# 25_Clocks_1.net
KiCad netlist of a schematic drawn in Altium Designer
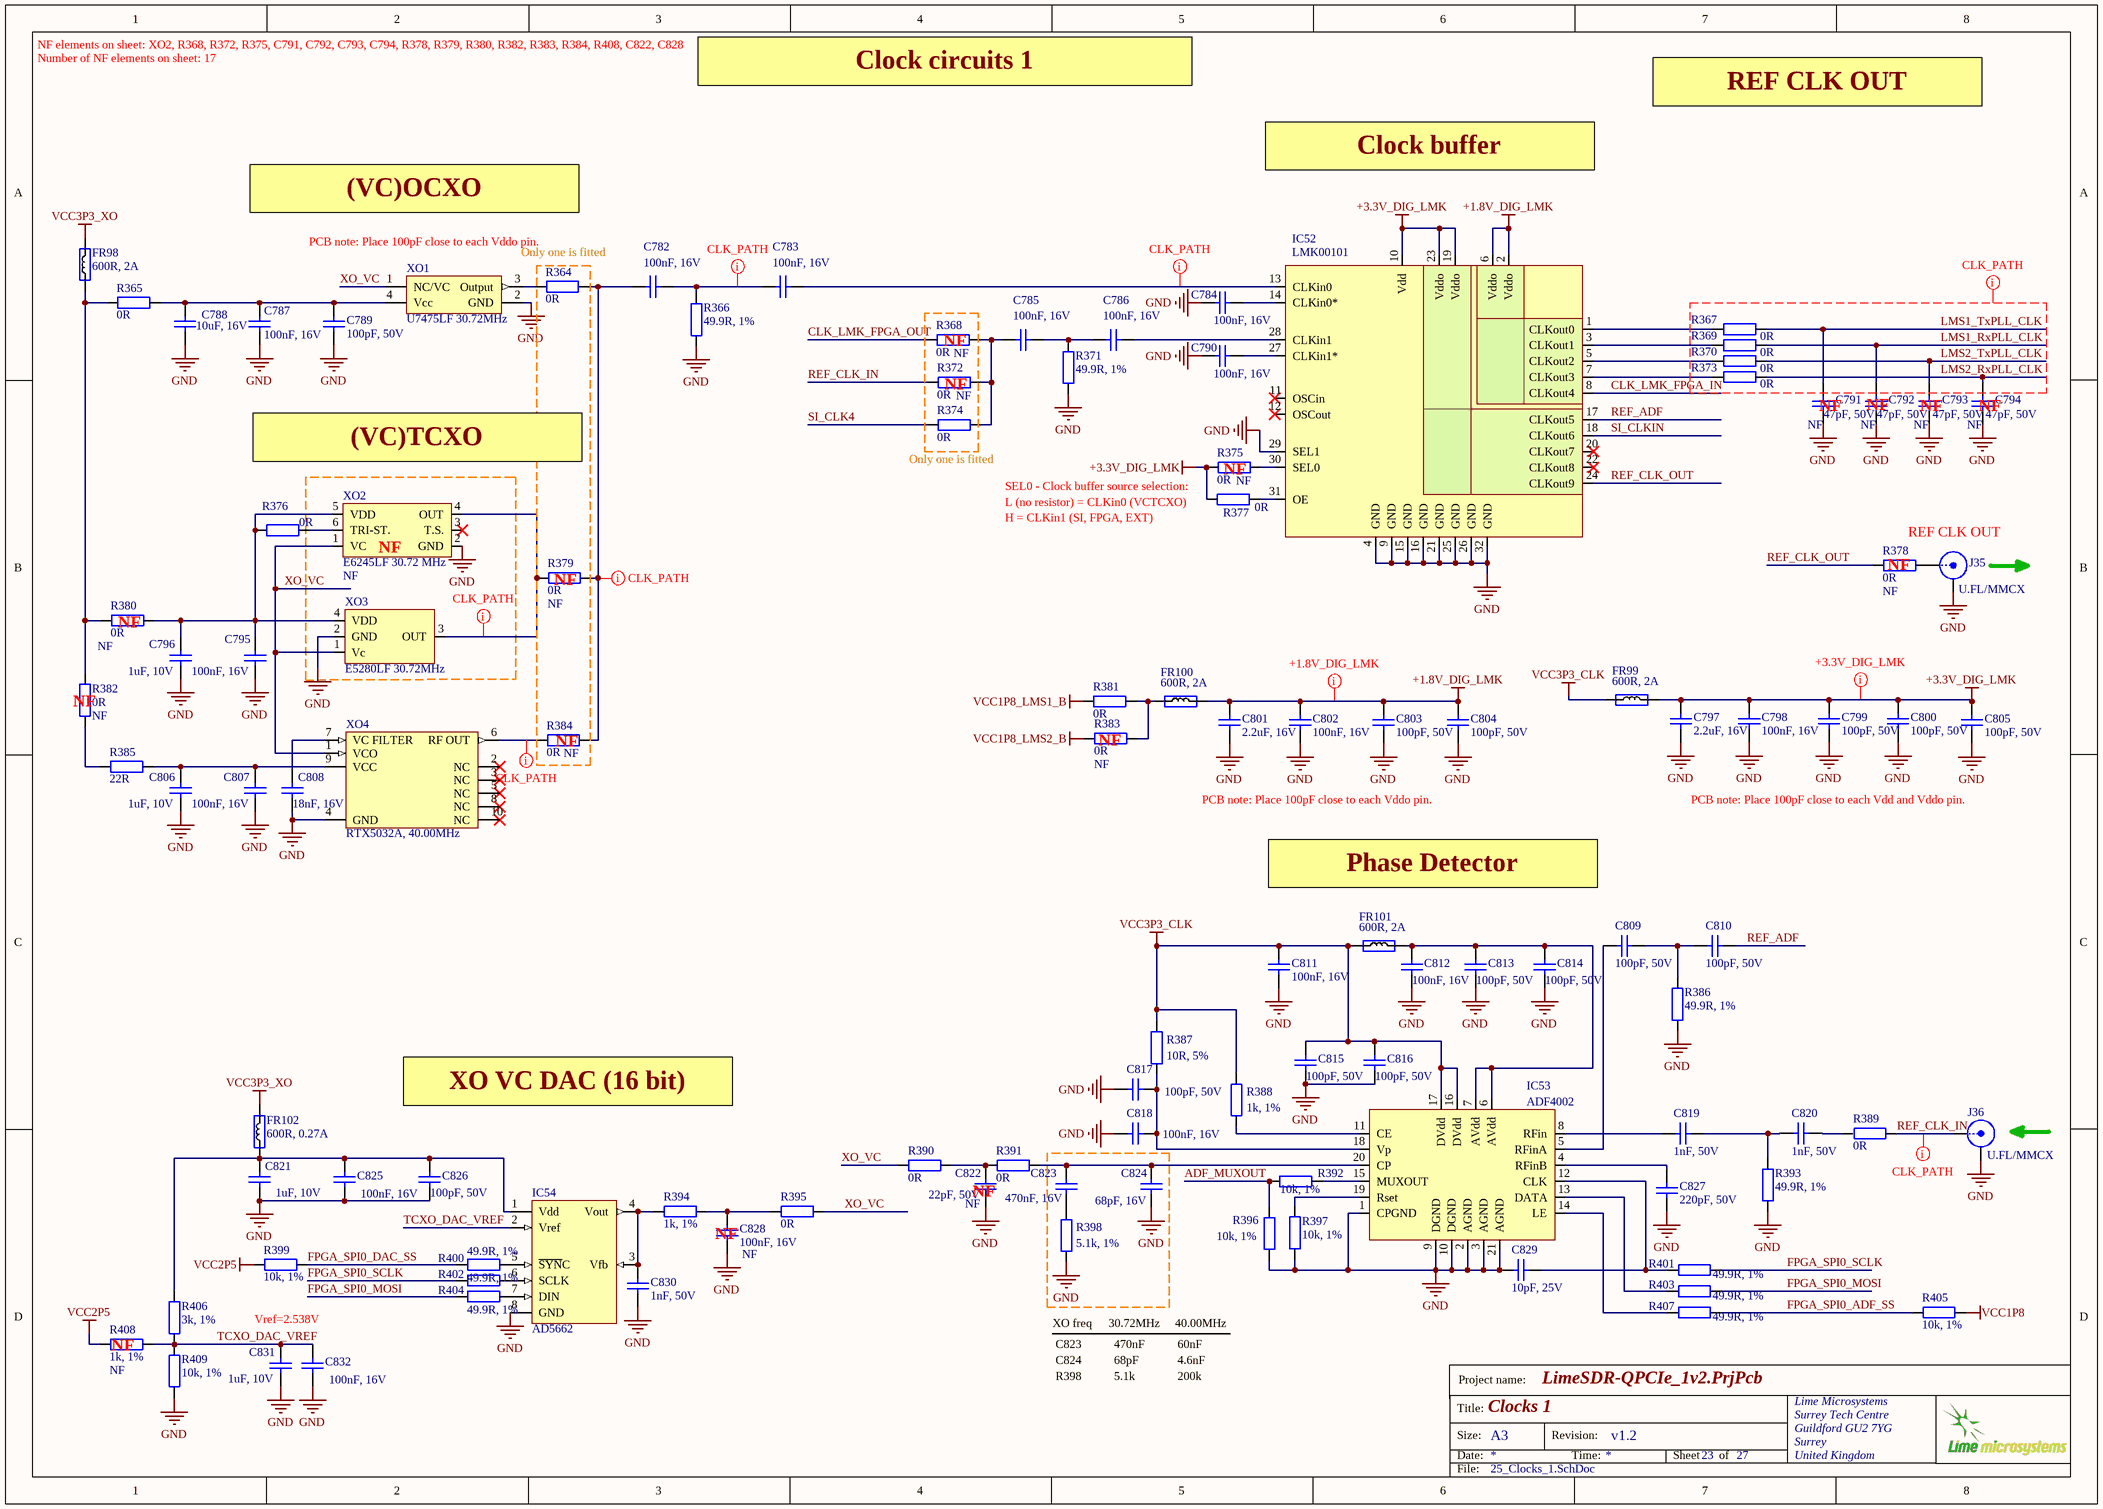
[diagram p0: 25_Clocks_1.SchDoc]

(export (version "E")
  (design (tool "Eeschema 10.0.6"))
  (components
    (comp (ref "C782")
      (value "100nF, 16V")
      (footprint "CAP0402")
      (fields
        (field (name "MANUFACTURER") "Murata Electronics")
        (field (name "TOLERANCE") "10 %")
        (field (name "MANUFACTURER PART NUMBER") "GRM155R71C104KA88D")
      )
      (libsource (lib "LimeMicroAltiumLib_schLib") (part "Cap_0402"))
    )
    (comp (ref "C783")
      (value "100nF, 16V")
      (footprint "CAP0402")
      (fields
        (field (name "MANUFACTURER") "Murata Electronics")
        (field (name "TOLERANCE") "10 %")
        (field (name "MANUFACTURER PART NUMBER") "GRM155R71C104KA88D")
      )
      (libsource (lib "LimeMicroAltiumLib_schLib") (part "Cap_0402"))
    )
    (comp (ref "C784")
      (value "100nF, 16V")
      (footprint "CAP0402")
      (fields
        (field (name "MANUFACTURER") "Murata Electronics")
        (field (name "TOLERANCE") "10 %")
        (field (name "MANUFACTURER PART NUMBER") "GRM155R71C104KA88D")
      )
      (libsource (lib "LimeMicroAltiumLib_schLib") (part "Cap_0402"))
    )
    (comp (ref "C785")
      (value "100nF, 16V")
      (footprint "CAP0402")
      (fields
        (field (name "MANUFACTURER") "Murata Electronics")
        (field (name "TOLERANCE") "10 %")
        (field (name "MANUFACTURER PART NUMBER") "GRM155R71C104KA88D")
      )
      (libsource (lib "LimeMicroAltiumLib_schLib") (part "Cap_0402"))
    )
    (comp (ref "C786")
      (value "100nF, 16V")
      (footprint "CAP0402")
      (fields
        (field (name "MANUFACTURER") "Murata Electronics")
        (field (name "TOLERANCE") "10 %")
        (field (name "MANUFACTURER PART NUMBER") "GRM155R71C104KA88D")
      )
      (libsource (lib "LimeMicroAltiumLib_schLib") (part "Cap_0402"))
    )
    (comp (ref "C787")
      (value "100nF, 16V")
      (footprint "CAP0402")
      (fields
        (field (name "MANUFACTURER") "Murata Electronics")
        (field (name "TOLERANCE") "10 %")
        (field (name "MANUFACTURER PART NUMBER") "GRM155R71C104KA88D")
      )
      (libsource (lib "LimeMicroAltiumLib_schLib") (part "Cap_0402"))
    )
    (comp (ref "C788")
      (value "10uF, 16V")
      (footprint "CAP0603")
      (fields (field (name "MANUFACTURER") "Yageo") (field (name "TOLERANCE") "±20%"))
      (libsource (lib "LimeMicroAltiumLib_schLib") (part "Cap_0603"))
    )
    (comp (ref "C789")
      (value "100pF, 50V")
      (footprint "CAP0402")
      (fields (field (name "TOLERANCE") "±5%") (field (name "MANUFACTURER") "Yageo"))
      (libsource (lib "LimeMicroAltiumLib_schLib") (part "Cap_0402"))
    )
    (comp (ref "C790")
      (value "100nF, 16V")
      (footprint "CAP0402")
      (fields
        (field (name "MANUFACTURER") "Murata Electronics")
        (field (name "TOLERANCE") "10 %")
        (field (name "MANUFACTURER PART NUMBER") "GRM155R71C104KA88D")
      )
      (libsource (lib "LimeMicroAltiumLib_schLib") (part "Cap_0402"))
    )
    (comp (ref "C791")
      (value "47pF, 50V")
      (footprint "CAP0402")
      (fields
        (field (name "TOLERANCE") "±1%")
        (field (name "MANUFACTURER") "TDK Corporation")
        (field (name "ASSEMBLY INFO") "NF")
      )
      (libsource (lib "LimeMicroAltiumLib_schLib") (part "Cap_0402"))
    )
    (comp (ref "C792")
      (value "47pF, 50V")
      (footprint "CAP0402")
      (fields
        (field (name "TOLERANCE") "±1%")
        (field (name "MANUFACTURER") "TDK Corporation")
        (field (name "ASSEMBLY INFO") "NF")
      )
      (libsource (lib "LimeMicroAltiumLib_schLib") (part "Cap_0402"))
    )
    (comp (ref "C793")
      (value "47pF, 50V")
      (footprint "CAP0402")
      (fields
        (field (name "TOLERANCE") "±1%")
        (field (name "MANUFACTURER") "TDK Corporation")
        (field (name "ASSEMBLY INFO") "NF")
      )
      (libsource (lib "LimeMicroAltiumLib_schLib") (part "Cap_0402"))
    )
    (comp (ref "C794")
      (value "47pF, 50V")
      (footprint "CAP0402")
      (fields
        (field (name "TOLERANCE") "±1%")
        (field (name "MANUFACTURER") "TDK Corporation")
        (field (name "ASSEMBLY INFO") "NF")
      )
      (libsource (lib "LimeMicroAltiumLib_schLib") (part "Cap_0402"))
    )
    (comp (ref "C795")
      (value "100nF, 16V")
      (footprint "CAP0402")
      (fields
        (field (name "MANUFACTURER") "Murata Electronics")
        (field (name "TOLERANCE") "10 %")
        (field (name "MANUFACTURER PART NUMBER") "GRM155R71C104KA88D")
      )
      (libsource (lib "LimeMicroAltiumLib_schLib") (part "Cap_0402"))
    )
    (comp (ref "C796")
      (value "1uF, 10V")
      (footprint "CAP0402")
      (fields (field (name "MANUFACTURER") "TDK"))
      (libsource (lib "LimeMicroAltiumLib_schLib") (part "Cap_0402"))
    )
    (comp (ref "C797")
      (value "2.2uF, 16V")
      (footprint "CAP0402")
      (description "CAP CER 2.2UF 16V 10% X5R 0402")
      (fields (field (name "MANUFACTURER") "TDK Corporation") (field (name "TOLERANCE") "±20%"))
      (libsource (lib "LimeMicroAltiumLib_schLib") (part "Cap_0402"))
    )
    (comp (ref "C798")
      (value "100nF, 16V")
      (footprint "CAP0402")
      (fields
        (field (name "MANUFACTURER") "Murata Electronics")
        (field (name "TOLERANCE") "10 %")
        (field (name "MANUFACTURER PART NUMBER") "GRM155R71C104KA88D")
      )
      (libsource (lib "LimeMicroAltiumLib_schLib") (part "Cap_0402"))
    )
    (comp (ref "C799")
      (value "100pF, 50V")
      (footprint "CAP0402")
      (fields (field (name "MANUFACTURER") "Yageo") (field (name "TOLERANCE") "±5%"))
      (libsource (lib "LimeMicroAltiumLib_schLib") (part "Cap_0402"))
    )
    (comp (ref "C800")
      (value "100pF, 50V")
      (footprint "CAP0402")
      (fields (field (name "MANUFACTURER") "Yageo") (field (name "TOLERANCE") "±5%"))
      (libsource (lib "LimeMicroAltiumLib_schLib") (part "Cap_0402"))
    )
    (comp (ref "C801")
      (value "2.2uF, 16V")
      (footprint "CAP0402")
      (description "CAP CER 2.2UF 16V 10% X5R 0402")
      (fields (field (name "MANUFACTURER") "TDK Corporation") (field (name "TOLERANCE") "±20%"))
      (libsource (lib "LimeMicroAltiumLib_schLib") (part "Cap_0402"))
    )
    (comp (ref "C802")
      (value "100nF, 16V")
      (footprint "CAP0402")
      (fields
        (field (name "MANUFACTURER") "Murata Electronics")
        (field (name "TOLERANCE") "10 %")
        (field (name "MANUFACTURER PART NUMBER") "GRM155R71C104KA88D")
      )
      (libsource (lib "LimeMicroAltiumLib_schLib") (part "Cap_0402"))
    )
    (comp (ref "C803")
      (value "100pF, 50V")
      (footprint "CAP0402")
      (fields (field (name "MANUFACTURER") "Yageo") (field (name "TOLERANCE") "±5%"))
      (libsource (lib "LimeMicroAltiumLib_schLib") (part "Cap_0402"))
    )
    (comp (ref "C804")
      (value "100pF, 50V")
      (footprint "CAP0402")
      (fields (field (name "MANUFACTURER") "Yageo") (field (name "TOLERANCE") "±5%"))
      (libsource (lib "LimeMicroAltiumLib_schLib") (part "Cap_0402"))
    )
    (comp (ref "C805")
      (value "100pF, 50V")
      (footprint "CAP0402")
      (fields (field (name "MANUFACTURER") "Yageo") (field (name "TOLERANCE") "±5%"))
      (libsource (lib "LimeMicroAltiumLib_schLib") (part "Cap_0402"))
    )
    (comp (ref "C806")
      (value "1uF, 10V")
      (footprint "CAP0402")
      (fields (field (name "MANUFACTURER") "TDK"))
      (libsource (lib "LimeMicroAltiumLib_schLib") (part "Cap_0402"))
    )
    (comp (ref "C807")
      (value "100nF, 16V")
      (footprint "CAP0402")
      (fields
        (field (name "MANUFACTURER") "Murata Electronics")
        (field (name "TOLERANCE") "10 %")
        (field (name "MANUFACTURER PART NUMBER") "GRM155R71C104KA88D")
      )
      (libsource (lib "LimeMicroAltiumLib_schLib") (part "Cap_0402"))
    )
    (comp (ref "C808")
      (value "18nF, 16V")
      (footprint "CAP0402")
      (fields (field (name "MANUFACTURER") "Yageo") (field (name "TOLERANCE") "±10%"))
      (libsource (lib "LimeMicroAltiumLib_schLib") (part "Cap_0402"))
    )
    (comp (ref "C809")
      (value "100pF, 50V")
      (footprint "CAP0402")
      (fields (field (name "MANUFACTURER") "Yageo") (field (name "TOLERANCE") "±5%"))
      (libsource (lib "LimeMicroAltiumLib_schLib") (part "Cap_0402"))
    )
    (comp (ref "C810")
      (value "100pF, 50V")
      (footprint "CAP0402")
      (fields (field (name "MANUFACTURER") "Yageo") (field (name "TOLERANCE") "±5%"))
      (libsource (lib "LimeMicroAltiumLib_schLib") (part "Cap_0402"))
    )
    (comp (ref "C811")
      (value "100nF, 16V")
      (footprint "CAP0402")
      (fields
        (field (name "MANUFACTURER") "Murata Electronics")
        (field (name "TOLERANCE") "10 %")
        (field (name "MANUFACTURER PART NUMBER") "GRM155R71C104KA88D")
      )
      (libsource (lib "LimeMicroAltiumLib_schLib") (part "Cap_0402"))
    )
    (comp (ref "C812")
      (value "100nF, 16V")
      (footprint "CAP0402")
      (fields
        (field (name "MANUFACTURER") "Murata Electronics")
        (field (name "TOLERANCE") "10 %")
        (field (name "MANUFACTURER PART NUMBER") "GRM155R71C104KA88D")
      )
      (libsource (lib "LimeMicroAltiumLib_schLib") (part "Cap_0402"))
    )
    (comp (ref "C813")
      (value "100pF, 50V")
      (footprint "CAP0402")
      (fields (field (name "MANUFACTURER") "Yageo") (field (name "TOLERANCE") "±5%"))
      (libsource (lib "LimeMicroAltiumLib_schLib") (part "Cap_0402"))
    )
    (comp (ref "C814")
      (value "100pF, 50V")
      (footprint "CAP0402")
      (fields (field (name "MANUFACTURER") "Yageo") (field (name "TOLERANCE") "±5%"))
      (libsource (lib "LimeMicroAltiumLib_schLib") (part "Cap_0402"))
    )
    (comp (ref "C815")
      (value "100pF, 50V")
      (footprint "CAP0402")
      (fields (field (name "MANUFACTURER") "Yageo") (field (name "TOLERANCE") "±5%"))
      (libsource (lib "LimeMicroAltiumLib_schLib") (part "Cap_0402"))
    )
    (comp (ref "C816")
      (value "100pF, 50V")
      (footprint "CAP0402")
      (fields (field (name "MANUFACTURER") "Yageo") (field (name "TOLERANCE") "±5%"))
      (libsource (lib "LimeMicroAltiumLib_schLib") (part "Cap_0402"))
    )
    (comp (ref "C817")
      (value "100pF, 50V")
      (footprint "CAP0402")
      (fields (field (name "MANUFACTURER") "Yageo") (field (name "TOLERANCE") "±5%"))
      (libsource (lib "LimeMicroAltiumLib_schLib") (part "Cap_0402"))
    )
    (comp (ref "C818")
      (value "100nF, 16V")
      (footprint "CAP0402")
      (fields
        (field (name "MANUFACTURER") "Murata Electronics")
        (field (name "TOLERANCE") "10 %")
        (field (name "MANUFACTURER PART NUMBER") "GRM155R71C104KA88D")
      )
      (libsource (lib "LimeMicroAltiumLib_schLib") (part "Cap_0402"))
    )
    (comp (ref "C819")
      (value "1nF, 50V")
      (footprint "CAP0402")
      (fields (field (name "TOLERANCE") "10 %") (field (name "MANUFACTURER") "Murata Electronics"))
      (libsource (lib "LimeMicroAltiumLib_schLib") (part "Cap_0402"))
    )
    (comp (ref "C820")
      (value "1nF, 50V")
      (footprint "CAP0402")
      (fields (field (name "TOLERANCE") "10 %") (field (name "MANUFACTURER") "Murata Electronics"))
      (libsource (lib "LimeMicroAltiumLib_schLib") (part "Cap_0402"))
    )
    (comp (ref "C821")
      (value "1uF, 10V")
      (footprint "CAP0402")
      (fields (field (name "MANUFACTURER") "TDK"))
      (libsource (lib "LimeMicroAltiumLib_schLib") (part "Cap_0402"))
    )
    (comp (ref "C822")
      (value "22pF, 50V")
      (footprint "CAP0402")
      (fields
        (field (name "ASSEMBLY INFO") "NF")
        (field (name "TOLERANCE") "±5%")
        (field (name "MANUFACTURER") "Yageo")
      )
      (libsource (lib "LimeMicroAltiumLib_schLib") (part "Cap_0402"))
    )
    (comp (ref "C823")
      (value "470nF, 16V")
      (footprint "CAP0402")
      (fields (field (name "MANUFACTURER") "Yageo") (field (name "TOLERANCE") "-20%, +80%"))
      (libsource (lib "LimeMicroAltiumLib_schLib") (part "Cap_0402"))
    )
    (comp (ref "C824")
      (value "68pF, 16V")
      (footprint "CAP0402")
      (fields (field (name "MANUFACTURER") "Wurth Electronics Inc.") (field (name "TOLERANCE") "±5%"))
      (libsource (lib "LimeMicroAltiumLib_schLib") (part "Cap_0402"))
    )
    (comp (ref "C825")
      (value "100nF, 16V")
      (footprint "CAP0402")
      (fields
        (field (name "TOLERANCE") "10 %")
        (field (name "MANUFACTURER") "Murata Electronics")
        (field (name "MANUFACTURER PART NUMBER") "GRM155R71C104KA88D")
      )
      (libsource (lib "LimeFPGAboard_schLib") (part "Cap_0603"))
    )
    (comp (ref "C826")
      (value "100pF, 50V")
      (footprint "CAP0402")
      (fields (field (name "MANUFACTURER") "Yageo") (field (name "TOLERANCE") "±5%"))
      (libsource (lib "LimeMicroAltiumLib_schLib") (part "Cap_0402"))
    )
    (comp (ref "C827")
      (value "220pF, 50V")
      (footprint "CAP0402")
      (fields (field (name "MANUFACTURER") "Yageo") (field (name "TOLERANCE") "±10%"))
      (libsource (lib "LimeMicroAltiumLib_schLib") (part "Cap_0402"))
    )
    (comp (ref "C828")
      (value "100nF, 16V")
      (footprint "CAP0402")
      (fields
        (field (name "ASSEMBLY INFO") "NF")
        (field (name "MANUFACTURER") "Murata Electronics")
        (field (name "TOLERANCE") "10 %")
        (field (name "MANUFACTURER PART NUMBER") "GRM155R71C104KA88D")
      )
      (libsource (lib "LimeMicroAltiumLib_schLib") (part "Cap_0402"))
    )
    (comp (ref "C829")
      (value "10pF, 25V")
      (footprint "CAP0402")
      (fields (field (name "MANUFACTURER") "AVX"))
      (libsource (lib "LimeMicroAltiumLib_schLib") (part "Cap_0402"))
    )
    (comp (ref "C830")
      (value "1nF, 50V")
      (footprint "CAP0402")
      (fields (field (name "TOLERANCE") "10 %") (field (name "MANUFACTURER") "Murata Electronics"))
      (libsource (lib "LimeMicroAltiumLib_schLib") (part "Cap_0402"))
    )
    (comp (ref "C831")
      (value "1uF, 10V")
      (footprint "CAP0402")
      (fields (field (name "MANUFACTURER") "TDK"))
      (libsource (lib "LimeMicroAltiumLib_schLib") (part "Cap_0402"))
    )
    (comp (ref "C832")
      (value "100nF, 16V")
      (footprint "CAP0402")
      (fields
        (field (name "TOLERANCE") "10 %")
        (field (name "MANUFACTURER") "Murata Electronics")
        (field (name "MANUFACTURER PART NUMBER") "GRM155R71C104KA88D")
      )
      (libsource (lib "LimeFPGAboard_schLib") (part "Cap_0603"))
    )
    (comp (ref "FR98")
      (value "600R, 2A")
      (footprint "RES0805")
      (fields (field (name "MANUFACTURER") "TDK"))
      (libsource (lib "LimeFPGAboard_schLib") (part "Ferrite"))
    )
    (comp (ref "FR99")
      (value "600R, 2A")
      (footprint "RES0805")
      (fields (field (name "MANUFACTURER") "TDK"))
      (libsource (lib "LimeMicroAltiumLib_schLib") (part "Ferrite"))
    )
    (comp (ref "FR100")
      (value "600R, 2A")
      (footprint "RES0805")
      (fields (field (name "MANUFACTURER") "TDK"))
      (libsource (lib "LimeMicroAltiumLib_schLib") (part "Ferrite"))
    )
    (comp (ref "FR101")
      (value "600R, 2A")
      (footprint "RES0805")
      (fields (field (name "MANUFACTURER") "TDK"))
      (libsource (lib "LimeMicroAltiumLib_schLib") (part "Ferrite"))
    )
    (comp (ref "FR102")
      (value "600R, 0.27A")
      (footprint "RES0201")
      (fields (field (name "MANUFACTURER") "Taiyo Yuden") (field (name "Comment") "Ferrite"))
      (libsource (lib "LimeMicroAltiumLib_schLib") (part "Ferrite"))
    )
    (comp (ref "IC52")
      (value "LMK00101")
      (footprint "LMK00101_WQFN32")
      (fields (field (name "MANUFACTURER") "Texas Instruments"))
      (libsource (lib "LimeMicroAltiumLib_schLib") (part "LMK00101"))
    )
    (comp (ref "IC53")
      (value "ADF4002")
      (footprint "ADF4002")
      (fields (field (name "MANUFACTURER") "Analog Devices Inc"))
      (libsource (lib "LimeMicroAltiumLib_schLib") (part "ADF4002"))
    )
    (comp (ref "IC54")
      (value "AD5662")
      (footprint "AD5662_SOT23-8")
      (fields (field (name "MANUFACTURER") "Analog Devices Inc."))
      (libsource (lib "LimeMicroAltiumLib_schLib") (part "AD5662"))
    )
    (comp (ref "J35")
      (value "U.FL/MMCX")
      (footprint "MMCX_UFL_conn_u")
      (fields (field (name "MANUFACTURER") "Molex, LLC"))
      (libsource (lib "LimeMicroAltiumLib_schLib") (part "RF_IF_connector"))
    )
    (comp (ref "J36")
      (value "U.FL/MMCX")
      (footprint "MMCX_UFL_conn_u")
      (description "CONN UMC RCPT STR 50 OHM SMD")
      (fields (field (name "MANUFACTURER") "Molex, LLC"))
      (libsource (lib "LimeMicroAltiumLib_schLib") (part "RF_IF_connector"))
    )
    (comp (ref "R364")
      (value "0R")
      (footprint "RES0402_v2")
      (fields (field (name "MANUFACTURER") "Yageo") (field (name "TOLERANCE") "Jumper"))
      (libsource (lib "LimeMicroAltiumLib_schLib") (part "Res_0402"))
    )
    (comp (ref "R365")
      (value "0R")
      (footprint "RES0402")
      (fields (field (name "MANUFACTURER") "Yageo") (field (name "TOLERANCE") "Jumper"))
      (libsource (lib "LimeMicroAltiumLib_schLib") (part "Res_0402"))
    )
    (comp (ref "R366")
      (value "49.9R, 1%")
      (footprint "RES0402")
      (fields
        (field (name "TOLERANCE") "±1%")
        (field (name "MANUFACTURER") "Samsung Electro-Mechanics America, Inc.")
      )
      (libsource (lib "LimeMicroAltiumLib_schLib") (part "Res_0402"))
    )
    (comp (ref "R367")
      (value "0R")
      (footprint "RES0402")
      (fields (field (name "MANUFACTURER") "Yageo") (field (name "TOLERANCE") "Jumper"))
      (libsource (lib "LimeMicroAltiumLib_schLib") (part "Res_0402"))
    )
    (comp (ref "R368")
      (value "0R")
      (footprint "RES0402_v2")
      (fields
        (field (name "ASSEMBLY INFO") "NF")
        (field (name "MANUFACTURER") "Yageo")
        (field (name "TOLERANCE") "Jumper")
      )
      (libsource (lib "LimeMicroAltiumLib_schLib") (part "Res_0402"))
    )
    (comp (ref "R369")
      (value "0R")
      (footprint "RES0402")
      (fields (field (name "MANUFACTURER") "Yageo") (field (name "TOLERANCE") "Jumper"))
      (libsource (lib "LimeMicroAltiumLib_schLib") (part "Res_0402"))
    )
    (comp (ref "R370")
      (value "0R")
      (footprint "RES0402")
      (fields (field (name "MANUFACTURER") "Yageo") (field (name "TOLERANCE") "Jumper"))
      (libsource (lib "LimeMicroAltiumLib_schLib") (part "Res_0402"))
    )
    (comp (ref "R371")
      (value "49.9R, 1%")
      (footprint "RES0402")
      (fields
        (field (name "TOLERANCE") "±1%")
        (field (name "MANUFACTURER") "Samsung Electro-Mechanics America, Inc.")
      )
      (libsource (lib "LimeMicroAltiumLib_schLib") (part "Res_0402"))
    )
    (comp (ref "R372")
      (value "0R")
      (footprint "RES0402_v2")
      (fields
        (field (name "ASSEMBLY INFO") "NF")
        (field (name "MANUFACTURER") "Yageo")
        (field (name "TOLERANCE") "Jumper")
      )
      (libsource (lib "LimeMicroAltiumLib_schLib") (part "Res_0402"))
    )
    (comp (ref "R373")
      (value "0R")
      (footprint "RES0402")
      (fields (field (name "MANUFACTURER") "Yageo") (field (name "TOLERANCE") "Jumper"))
      (libsource (lib "LimeMicroAltiumLib_schLib") (part "Res_0402"))
    )
    (comp (ref "R374")
      (value "0R")
      (footprint "RES0402_v2")
      (fields (field (name "MANUFACTURER") "Yageo") (field (name "TOLERANCE") "Jumper"))
      (libsource (lib "LimeMicroAltiumLib_schLib") (part "Res_0402"))
    )
    (comp (ref "R375")
      (value "0R")
      (footprint "RES0402")
      (fields
        (field (name "ASSEMBLY INFO") "NF")
        (field (name "MANUFACTURER") "Yageo")
        (field (name "TOLERANCE") "Jumper")
      )
      (libsource (lib "LimeMicroAltiumLib_schLib") (part "Res_0402"))
    )
    (comp (ref "R376")
      (value "0R")
      (footprint "RES0402")
      (fields (field (name "MANUFACTURER") "Yageo") (field (name "TOLERANCE") "Jumper"))
      (libsource (lib "LimeMicroAltiumLib_schLib") (part "Res_0402"))
    )
    (comp (ref "R377")
      (value "0R")
      (footprint "RES0402")
      (fields (field (name "MANUFACTURER") "Yageo") (field (name "TOLERANCE") "Jumper"))
      (libsource (lib "LimeMicroAltiumLib_schLib") (part "Res_0402"))
    )
    (comp (ref "R378")
      (value "0R")
      (footprint "RES0402")
      (fields
        (field (name "ASSEMBLY INFO") "NF")
        (field (name "MANUFACTURER") "Yageo")
        (field (name "TOLERANCE") "Jumper")
      )
      (libsource (lib "LimeMicroAltiumLib_schLib") (part "Res_0402"))
    )
    (comp (ref "R379")
      (value "0R")
      (footprint "RES0402_v2")
      (fields
        (field (name "ASSEMBLY INFO") "NF")
        (field (name "MANUFACTURER") "Yageo")
        (field (name "TOLERANCE") "Jumper")
      )
      (libsource (lib "LimeMicroAltiumLib_schLib") (part "Res_0402"))
    )
    (comp (ref "R380")
      (value "0R")
      (footprint "RES0402")
      (fields
        (field (name "MANUFACTURER") "Yageo")
        (field (name "TOLERANCE") "Jumper")
        (field (name "ASSEMBLY INFO") "NF")
      )
      (libsource (lib "LimeMicroAltiumLib_schLib") (part "Res_0402"))
    )
    (comp (ref "R381")
      (value "0R")
      (footprint "RES0402")
      (fields (field (name "MANUFACTURER") "Yageo") (field (name "TOLERANCE") "Jumper"))
      (libsource (lib "LimeMicroAltiumLib_schLib") (part "Res_0402"))
    )
    (comp (ref "R382")
      (value "0R")
      (footprint "RES0402")
      (fields
        (field (name "ASSEMBLY INFO") "NF")
        (field (name "MANUFACTURER") "Yageo")
        (field (name "TOLERANCE") "Jumper")
      )
      (libsource (lib "LimeMicroAltiumLib_schLib") (part "Res_0402"))
    )
    (comp (ref "R383")
      (value "0R")
      (footprint "RES0402")
      (fields
        (field (name "ASSEMBLY INFO") "NF")
        (field (name "MANUFACTURER") "Yageo")
        (field (name "TOLERANCE") "Jumper")
      )
      (libsource (lib "LimeMicroAltiumLib_schLib") (part "Res_0402"))
    )
    (comp (ref "R384")
      (value "0R")
      (footprint "RES0402_v2")
      (fields
        (field (name "ASSEMBLY INFO") "NF")
        (field (name "MANUFACTURER") "Yageo")
        (field (name "TOLERANCE") "Jumper")
      )
      (libsource (lib "LimeMicroAltiumLib_schLib") (part "Res_0402"))
    )
    (comp (ref "R385")
      (value "22R")
      (footprint "RES0402")
      (fields (field (name "TOLERANCE") "±1%") (field (name "MANUFACTURER") "Yageo"))
      (libsource (lib "LimeFPGAboard_schLib") (part "Res_0402"))
    )
    (comp (ref "R386")
      (value "49.9R, 1%")
      (footprint "RES0402")
      (fields
        (field (name "TOLERANCE") "±1%")
        (field (name "MANUFACTURER") "Samsung Electro-Mechanics America, Inc.")
      )
      (libsource (lib "LimeMicroAltiumLib_schLib") (part "Res_0402"))
    )
    (comp (ref "R387")
      (value "10R, 5%")
      (footprint "RES0402")
      (fields (field (name "TOLERANCE") "±5%") (field (name "MANUFACTURER") "Yageo"))
      (libsource (lib "LimeMicroAltiumLib_schLib") (part "Res_0402"))
    )
    (comp (ref "R388")
      (value "1k, 1%")
      (footprint "RES0402")
      (fields (field (name "MANUFACTURER") "Stackpole Electronics Inc") (field (name "TOLERANCE") "±1%"))
      (libsource (lib "LimeMicroAltiumLib_schLib") (part "Res_0402"))
    )
    (comp (ref "R389")
      (value "0R")
      (footprint "RES0402_v2")
      (fields (field (name "MANUFACTURER") "Yageo") (field (name "TOLERANCE") "Jumper"))
      (libsource (lib "LimeMicroAltiumLib_schLib") (part "Res_0402"))
    )
    (comp (ref "R390")
      (value "0R")
      (footprint "RES0402")
      (fields (field (name "MANUFACTURER") "Yageo") (field (name "TOLERANCE") "Jumper"))
      (libsource (lib "LimeMicroAltiumLib_schLib") (part "Res_0402"))
    )
    (comp (ref "R391")
      (value "0R")
      (footprint "RES0402")
      (fields (field (name "MANUFACTURER") "Yageo") (field (name "TOLERANCE") "Jumper"))
      (libsource (lib "LimeMicroAltiumLib_schLib") (part "Res_0402"))
    )
    (comp (ref "R392")
      (value "10k, 1%")
      (footprint "RES0402")
      (fields (field (name "MANUFACTURER") "Yageo") (field (name "TOLERANCE") "±1%"))
      (libsource (lib "LimeMicroAltiumLib_schLib") (part "Res_0402"))
    )
    (comp (ref "R393")
      (value "49.9R, 1%")
      (footprint "RES0402")
      (fields
        (field (name "TOLERANCE") "±1%")
        (field (name "MANUFACTURER") "Samsung Electro-Mechanics America, Inc.")
      )
      (libsource (lib "LimeMicroAltiumLib_schLib") (part "Res_0402"))
    )
    (comp (ref "R394")
      (value "1k, 1%")
      (footprint "RES0402")
      (fields (field (name "MANUFACTURER") "Stackpole Electronics Inc") (field (name "TOLERANCE") "±1%"))
      (libsource (lib "LimeMicroAltiumLib_schLib") (part "Res_0402"))
    )
    (comp (ref "R395")
      (value "0R")
      (footprint "RES0402")
      (fields (field (name "MANUFACTURER") "Yageo") (field (name "TOLERANCE") "Jumper"))
      (libsource (lib "LimeMicroAltiumLib_schLib") (part "Res_0402"))
    )
    (comp (ref "R396")
      (value "10k, 1%")
      (footprint "RES0402")
      (fields (field (name "MANUFACTURER") "Yageo") (field (name "TOLERANCE") "±1%"))
      (libsource (lib "LimeMicroAltiumLib_schLib") (part "Res_0402"))
    )
    (comp (ref "R397")
      (value "10k, 1%")
      (footprint "RES0402")
      (fields (field (name "MANUFACTURER") "Yageo") (field (name "TOLERANCE") "±1%"))
      (libsource (lib "LimeMicroAltiumLib_schLib") (part "Res_0402"))
    )
    (comp (ref "R398")
      (value "5.1k, 1%")
      (footprint "RES0402")
      (fields (field (name "MANUFACTURER") "Yageo") (field (name "TOLERANCE") "±1%"))
      (libsource (lib "LimeMicroAltiumLib_schLib") (part "Res_0402"))
    )
    (comp (ref "R399")
      (value "10k, 1%")
      (footprint "RES0402")
      (fields (field (name "MANUFACTURER") "Yageo") (field (name "TOLERANCE") "±1%"))
      (libsource (lib "LimeMicroAltiumLib_schLib") (part "Res_0402"))
    )
    (comp (ref "R400")
      (value "49.9R, 1%")
      (footprint "RES0402")
      (fields
        (field (name "TOLERANCE") "±1%")
        (field (name "MANUFACTURER") "Samsung Electro-Mechanics America, Inc.")
      )
      (libsource (lib "LimeMicroAltiumLib_schLib") (part "Res_0402"))
    )
    (comp (ref "R401")
      (value "49.9R, 1%")
      (footprint "RES0402")
      (fields
        (field (name "TOLERANCE") "±1%")
        (field (name "MANUFACTURER") "Samsung Electro-Mechanics America, Inc.")
      )
      (libsource (lib "LimeMicroAltiumLib_schLib") (part "Res_0402"))
    )
    (comp (ref "R402")
      (value "49.9R, 1%")
      (footprint "RES0402")
      (fields
        (field (name "TOLERANCE") "±1%")
        (field (name "MANUFACTURER") "Samsung Electro-Mechanics America, Inc.")
      )
      (libsource (lib "LimeMicroAltiumLib_schLib") (part "Res_0402"))
    )
    (comp (ref "R403")
      (value "49.9R, 1%")
      (footprint "RES0402")
      (fields
        (field (name "TOLERANCE") "±1%")
        (field (name "MANUFACTURER") "Samsung Electro-Mechanics America, Inc.")
      )
      (libsource (lib "LimeMicroAltiumLib_schLib") (part "Res_0402"))
    )
    (comp (ref "R404")
      (value "49.9R, 1%")
      (footprint "RES0402")
      (fields
        (field (name "TOLERANCE") "±1%")
        (field (name "MANUFACTURER") "Samsung Electro-Mechanics America, Inc.")
      )
      (libsource (lib "LimeMicroAltiumLib_schLib") (part "Res_0402"))
    )
    (comp (ref "R405")
      (value "10k, 1%")
      (footprint "RES0402")
      (fields (field (name "MANUFACTURER") "Yageo") (field (name "TOLERANCE") "±1%"))
      (libsource (lib "LimeMicroAltiumLib_schLib") (part "Res_0402"))
    )
    (comp (ref "R406")
      (value "3k, 1%")
      (footprint "RES0402")
      (fields (field (name "TOLERANCE") "±1%") (field (name "MANUFACTURER") "Vishay Dale"))
      (libsource (lib "LimeMicroAltiumLib_schLib") (part "Res_0402"))
    )
    (comp (ref "R407")
      (value "49.9R, 1%")
      (footprint "RES0402")
      (fields
        (field (name "TOLERANCE") "±1%")
        (field (name "MANUFACTURER") "Samsung Electro-Mechanics America, Inc.")
      )
      (libsource (lib "LimeMicroAltiumLib_schLib") (part "Res_0402"))
    )
    (comp (ref "R408")
      (value "1k, 1%")
      (footprint "RES0402")
      (fields
        (field (name "ASSEMBLY INFO") "NF")
        (field (name "MANUFACTURER") "Stackpole Electronics Inc")
        (field (name "TOLERANCE") "±1%")
      )
      (libsource (lib "LimeMicroAltiumLib_schLib") (part "Res_0402"))
    )
    (comp (ref "R409")
      (value "10k, 1%")
      (footprint "RES0402")
      (fields (field (name "MANUFACTURER") "Yageo") (field (name "TOLERANCE") "±1%"))
      (libsource (lib "LimeMicroAltiumLib_schLib") (part "Res_0402"))
    )
    (comp (ref "XO1")
      (value "U7475LF 30.72MHz")
      (footprint "AOCJYR-10.000MHz")
      (fields (field (name "MANUFACTURER") "Rakon"))
      (libsource (lib "LimeMicroAltiumLib_schLib") (part "AOCJYR-10.000MHz"))
    )
    (comp (ref "XO2")
      (value "E6245LF 30.72 MHz")
      (footprint "RAKON_RPT7050A")
      (fields (field (name "ASSEMBLY INFO") "NF") (field (name "MANUFACTURER") "Rakon"))
      (libsource (lib "LimeMicroAltiumLib_schLib") (part "RPT7050A"))
    )
    (comp (ref "XO3")
      (value "E5280LF 30.72MHz")
      (footprint "RAKON_TXCO")
      (fields (field (name "MANUFACTURER") "Rakon"))
      (libsource (lib "LimeMicroAltiumLib_schLib") (part "TXCO"))
    )
    (comp (ref "XO4")
      (value "RTX5032A, 40.00MHz")
      (footprint "RAKON_RTX5032A")
      (fields (field (name "MANUFACTURER") "Rakon"))
      (libsource (lib "LimeMicroAltiumLib_schLib") (part "Rakon_RTX5032A"))
    )
  )
  (nets
    (net (code "1") (name "+1.8V_DIG_LMK") (class "Default")
      (node (ref "C801") (pin "2") (pinfunction "2_2") (pintype "passive"))
      (node (ref "C802") (pin "2") (pinfunction "2_2") (pintype "passive"))
      (node (ref "C803") (pin "2") (pinfunction "2_2") (pintype "passive"))
      (node (ref "C804") (pin "2") (pinfunction "2_2") (pintype "passive"))
      (node (ref "FR100") (pin "2") (pinfunction "2_2") (pintype "passive"))
      (node (ref "IC52") (pin "2") (pinfunction "Vddo_2") (pintype "power_in"))
      (node (ref "IC52") (pin "6") (pinfunction "Vddo_6") (pintype "power_in"))
    )
    (net (code "2") (name "+3.3V_DIG_LMK") (class "Default")
      (node (ref "C797") (pin "2") (pinfunction "2_2") (pintype "passive"))
      (node (ref "C798") (pin "2") (pinfunction "2_2") (pintype "passive"))
      (node (ref "C799") (pin "2") (pinfunction "2_2") (pintype "passive"))
      (node (ref "C800") (pin "2") (pinfunction "2_2") (pintype "passive"))
      (node (ref "C805") (pin "2") (pinfunction "2_2") (pintype "passive"))
      (node (ref "FR99") (pin "2") (pinfunction "2_2") (pintype "passive"))
      (node (ref "IC52") (pin "10") (pinfunction "Vdd_10") (pintype "power_in"))
      (node (ref "IC52") (pin "19") (pinfunction "Vddo_19") (pintype "power_in"))
      (node (ref "IC52") (pin "23") (pinfunction "Vddo_23") (pintype "power_in"))
      (node (ref "R375") (pin "2") (pinfunction "2_2") (pintype "passive"))
      (node (ref "R377") (pin "1") (pinfunction "1_1") (pintype "passive"))
    )
    (net (code "3") (name "/ADF_MUXOUT") (class "Default")
      (node (ref "R392") (pin "1") (pinfunction "1_1") (pintype "passive"))
      (node (ref "R396") (pin "1") (pinfunction "1_1") (pintype "passive"))
    )
    (net (code "4") (name "/CLK_LMK_FPGA_IN") (class "Default")
      (node (ref "IC52") (pin "8") (pinfunction "CLKout4_8") (pintype "output"))
    )
    (net (code "5") (name "/CLK_LMK_FPGA_OUT") (class "Default")
      (node (ref "R368") (pin "1") (pinfunction "1_1") (pintype "passive"))
    )
    (net (code "6") (name "/FPGA_SPI0_ADF_SS") (class "Default")
      (node (ref "R405") (pin "1") (pinfunction "1_1") (pintype "passive"))
      (node (ref "R407") (pin "1") (pinfunction "1_1") (pintype "passive"))
    )
    (net (code "7") (name "/FPGA_SPI0_DAC_SS") (class "Default")
      (node (ref "R399") (pin "1") (pinfunction "1_1") (pintype "passive"))
      (node (ref "R400") (pin "2") (pinfunction "2_2") (pintype "passive"))
    )
    (net (code "8") (name "/FPGA_SPI0_MOSI") (class "Default")
      (node (ref "R403") (pin "1") (pinfunction "1_1") (pintype "passive"))
      (node (ref "R404") (pin "2") (pinfunction "2_2") (pintype "passive"))
    )
    (net (code "9") (name "/FPGA_SPI0_SCLK") (class "Default")
      (node (ref "R401") (pin "1") (pinfunction "1_1") (pintype "passive"))
      (node (ref "R402") (pin "2") (pinfunction "2_2") (pintype "passive"))
    )
    (net (code "10") (name "/LMS1_RxPLL_CLK") (class "Default")
      (node (ref "C792") (pin "2") (pinfunction "2_2") (pintype "passive"))
      (node (ref "R369") (pin "1") (pinfunction "1_1") (pintype "passive"))
    )
    (net (code "11") (name "/LMS1_TxPLL_CLK") (class "Default")
      (node (ref "C791") (pin "2") (pinfunction "2_2") (pintype "passive"))
      (node (ref "R367") (pin "1") (pinfunction "1_1") (pintype "passive"))
    )
    (net (code "12") (name "/LMS2_RxPLL_CLK") (class "Default")
      (node (ref "C794") (pin "2") (pinfunction "2_2") (pintype "passive"))
      (node (ref "R373") (pin "1") (pinfunction "1_1") (pintype "passive"))
    )
    (net (code "13") (name "/LMS2_TxPLL_CLK") (class "Default")
      (node (ref "C793") (pin "2") (pinfunction "2_2") (pintype "passive"))
      (node (ref "R370") (pin "1") (pinfunction "1_1") (pintype "passive"))
    )
    (net (code "14") (name "/REF_ADF") (class "Default")
      (node (ref "C810") (pin "2") (pinfunction "2_2") (pintype "passive"))
      (node (ref "IC52") (pin "17") (pinfunction "CLKout5_17") (pintype "output"))
    )
    (net (code "15") (name "/REF_CLK_IN") (class "Default")
      (node (ref "J36") (pin "1") (pinfunction "X_1") (pintype "passive"))
      (node (ref "R372") (pin "2") (pinfunction "2_2") (pintype "passive"))
      (node (ref "R389") (pin "1") (pinfunction "1_1") (pintype "passive"))
    )
    (net (code "16") (name "/REF_CLK_OUT") (class "Default")
      (node (ref "IC52") (pin "24") (pinfunction "CLKout9_24") (pintype "output"))
      (node (ref "R378") (pin "2") (pinfunction "2_2") (pintype "passive"))
    )
    (net (code "17") (name "/SI_CLK4") (class "Default")
      (node (ref "R374") (pin "2") (pinfunction "2_2") (pintype "passive"))
    )
    (net (code "18") (name "/SI_CLKIN") (class "Default")
      (node (ref "IC52") (pin "18") (pinfunction "CLKout6_18") (pintype "output"))
    )
    (net (code "19") (name "/TCXO_DAC_VREF") (class "Default")
      (node (ref "C831") (pin "2") (pinfunction "2_2") (pintype "passive"))
      (node (ref "C832") (pin "1") (pinfunction "1_1") (pintype "passive"))
      (node (ref "IC54") (pin "2") (pinfunction "Vref_2") (pintype "input"))
      (node (ref "R406") (pin "1") (pinfunction "1_1") (pintype "passive"))
      (node (ref "R408") (pin "1") (pinfunction "1_1") (pintype "passive"))
      (node (ref "R409") (pin "1") (pinfunction "1_1") (pintype "passive"))
    )
    (net (code "20") (name "/XO_VC") (class "Default")
      (node (ref "R390") (pin "2") (pinfunction "2_2") (pintype "passive"))
      (node (ref "R395") (pin "1") (pinfunction "1_1") (pintype "passive"))
      (node (ref "XO1") (pin "1") (pinfunction "NC/VC_1") (pintype "passive"))
      (node (ref "XO2") (pin "1") (pinfunction "VC_1") (pintype "passive"))
      (node (ref "XO3") (pin "1") (pinfunction "Vc_1") (pintype "passive"))
      (node (ref "XO4") (pin "1") (pinfunction "VCO_1") (pintype "input"))
    )
    (net (code "21") (name "GND") (class "Default")
      (node (ref "C784") (pin "1") (pinfunction "1_1") (pintype "passive"))
      (node (ref "C787") (pin "1") (pinfunction "1_1") (pintype "passive"))
      (node (ref "C788") (pin "1") (pinfunction "1_1") (pintype "passive"))
      (node (ref "C789") (pin "2") (pinfunction "2_2") (pintype "passive"))
      (node (ref "C790") (pin "1") (pinfunction "1_1") (pintype "passive"))
      (node (ref "C791") (pin "1") (pinfunction "1_1") (pintype "passive"))
      (node (ref "C792") (pin "1") (pinfunction "1_1") (pintype "passive"))
      (node (ref "C793") (pin "1") (pinfunction "1_1") (pintype "passive"))
      (node (ref "C794") (pin "1") (pinfunction "1_1") (pintype "passive"))
      (node (ref "C795") (pin "1") (pinfunction "1_1") (pintype "passive"))
      (node (ref "C796") (pin "1") (pinfunction "1_1") (pintype "passive"))
      (node (ref "C797") (pin "1") (pinfunction "1_1") (pintype "passive"))
      (node (ref "C798") (pin "1") (pinfunction "1_1") (pintype "passive"))
      (node (ref "C799") (pin "1") (pinfunction "1_1") (pintype "passive"))
      (node (ref "C800") (pin "1") (pinfunction "1_1") (pintype "passive"))
      (node (ref "C801") (pin "1") (pinfunction "1_1") (pintype "passive"))
      (node (ref "C802") (pin "1") (pinfunction "1_1") (pintype "passive"))
      (node (ref "C803") (pin "1") (pinfunction "1_1") (pintype "passive"))
      (node (ref "C804") (pin "1") (pinfunction "1_1") (pintype "passive"))
      (node (ref "C805") (pin "1") (pinfunction "1_1") (pintype "passive"))
      (node (ref "C806") (pin "1") (pinfunction "1_1") (pintype "passive"))
      (node (ref "C807") (pin "1") (pinfunction "1_1") (pintype "passive"))
      (node (ref "C808") (pin "1") (pinfunction "1_1") (pintype "passive"))
      (node (ref "C811") (pin "1") (pinfunction "1_1") (pintype "passive"))
      (node (ref "C812") (pin "1") (pinfunction "1_1") (pintype "passive"))
      (node (ref "C813") (pin "2") (pinfunction "2_2") (pintype "passive"))
      (node (ref "C814") (pin "2") (pinfunction "2_2") (pintype "passive"))
      (node (ref "C815") (pin "2") (pinfunction "2_2") (pintype "passive"))
      (node (ref "C816") (pin "2") (pinfunction "2_2") (pintype "passive"))
      (node (ref "C817") (pin "1") (pinfunction "1_1") (pintype "passive"))
      (node (ref "C818") (pin "2") (pinfunction "2_2") (pintype "passive"))
      (node (ref "C821") (pin "1") (pinfunction "1_1") (pintype "passive"))
      (node (ref "C822") (pin "1") (pinfunction "1_1") (pintype "passive"))
      (node (ref "C824") (pin "1") (pinfunction "1_1") (pintype "passive"))
      (node (ref "C825") (pin "2") (pinfunction "2_2") (pintype "passive"))
      (node (ref "C826") (pin "2") (pinfunction "2_2") (pintype "passive"))
      (node (ref "C827") (pin "2") (pinfunction "2_2") (pintype "passive"))
      (node (ref "C828") (pin "1") (pinfunction "1_1") (pintype "passive"))
      (node (ref "C829") (pin "1") (pinfunction "1_1") (pintype "passive"))
      (node (ref "C830") (pin "2") (pinfunction "2_2") (pintype "passive"))
      (node (ref "C831") (pin "1") (pinfunction "1_1") (pintype "passive"))
      (node (ref "C832") (pin "2") (pinfunction "2_2") (pintype "passive"))
      (node (ref "IC52") (pin "15") (pinfunction "GND_15") (pintype "passive"))
      (node (ref "IC52") (pin "16") (pinfunction "GND_16") (pintype "passive"))
      (node (ref "IC52") (pin "21") (pinfunction "GND_21") (pintype "passive"))
      (node (ref "IC52") (pin "25") (pinfunction "GND_25") (pintype "passive"))
      (node (ref "IC52") (pin "26") (pinfunction "GND_26") (pintype "passive"))
      (node (ref "IC52") (pin "29") (pinfunction "SEL1_29") (pintype "input"))
      (node (ref "IC52") (pin "32") (pinfunction "GND_32") (pintype "passive"))
      (node (ref "IC52") (pin "4") (pinfunction "GND_4") (pintype "passive"))
      (node (ref "IC52") (pin "9") (pinfunction "GND_9") (pintype "passive"))
      (node (ref "IC53") (pin "1") (pinfunction "CPGND_1") (pintype "passive"))
      (node (ref "IC53") (pin "10") (pinfunction "DGND_10") (pintype "passive"))
      (node (ref "IC53") (pin "2") (pinfunction "AGND_2") (pintype "passive"))
      (node (ref "IC53") (pin "21") (pinfunction "AGND_21") (pintype "passive"))
      (node (ref "IC53") (pin "3") (pinfunction "AGND_3") (pintype "passive"))
      (node (ref "IC53") (pin "9") (pinfunction "DGND_9") (pintype "passive"))
      (node (ref "IC54") (pin "8") (pinfunction "GND_8") (pintype "passive"))
      (node (ref "J35") (pin "2") (pinfunction "Y_2") (pintype "passive"))
      (node (ref "J36") (pin "2") (pinfunction "Y_2") (pintype "passive"))
      (node (ref "R366") (pin "1") (pinfunction "1_1") (pintype "passive"))
      (node (ref "R371") (pin "1") (pinfunction "1_1") (pintype "passive"))
      (node (ref "R386") (pin "1") (pinfunction "1_1") (pintype "passive"))
      (node (ref "R393") (pin "1") (pinfunction "1_1") (pintype "passive"))
      (node (ref "R396") (pin "2") (pinfunction "2_2") (pintype "passive"))
      (node (ref "R397") (pin "2") (pinfunction "2_2") (pintype "passive"))
      (node (ref "R398") (pin "1") (pinfunction "1_1") (pintype "passive"))
      (node (ref "R409") (pin "2") (pinfunction "2_2") (pintype "passive"))
      (node (ref "XO1") (pin "2") (pinfunction "GND_2") (pintype "passive"))
      (node (ref "XO2") (pin "2") (pinfunction "GND_2") (pintype "passive"))
      (node (ref "XO3") (pin "2") (pinfunction "GND_2") (pintype "passive"))
      (node (ref "XO4") (pin "4") (pinfunction "GND_4") (pintype "passive"))
    )
    (net (code "22") (name "Net-(C782-Pad1)") (class "Default")
      (node (ref "C782") (pin "1") (pinfunction "1_1") (pintype "passive"))
      (node (ref "C783") (pin "2") (pinfunction "2_2") (pintype "passive"))
      (node (ref "R366") (pin "2") (pinfunction "2_2") (pintype "passive"))
    )
    (net (code "23") (name "Net-(C782-Pad2)") (class "Default")
      (node (ref "C782") (pin "2") (pinfunction "2_2") (pintype "passive"))
      (node (ref "R364") (pin "1") (pinfunction "1_1") (pintype "passive"))
      (node (ref "R379") (pin "1") (pinfunction "1_1") (pintype "passive"))
      (node (ref "R384") (pin "2") (pinfunction "2_2") (pintype "passive"))
    )
    (net (code "24") (name "Net-(C785-Pad1)") (class "Default")
      (node (ref "C785") (pin "1") (pinfunction "1_1") (pintype "passive"))
      (node (ref "C786") (pin "2") (pinfunction "2_2") (pintype "passive"))
      (node (ref "R371") (pin "2") (pinfunction "2_2") (pintype "passive"))
    )
    (net (code "25") (name "Net-(C785-Pad2)") (class "Default")
      (node (ref "C785") (pin "2") (pinfunction "2_2") (pintype "passive"))
      (node (ref "R368") (pin "2") (pinfunction "2_2") (pintype "passive"))
      (node (ref "R372") (pin "1") (pinfunction "1_1") (pintype "passive"))
      (node (ref "R374") (pin "1") (pinfunction "1_1") (pintype "passive"))
    )
    (net (code "26") (name "Net-(C809-Pad2)") (class "Default")
      (node (ref "C809") (pin "2") (pinfunction "2_2") (pintype "passive"))
      (node (ref "C810") (pin "1") (pinfunction "1_1") (pintype "passive"))
      (node (ref "R386") (pin "2") (pinfunction "2_2") (pintype "passive"))
    )
    (net (code "27") (name "Net-(C812-Pad2)") (class "Default")
      (node (ref "C812") (pin "2") (pinfunction "2_2") (pintype "passive"))
      (node (ref "C813") (pin "1") (pinfunction "1_1") (pintype "passive"))
      (node (ref "C814") (pin "1") (pinfunction "1_1") (pintype "passive"))
      (node (ref "FR101") (pin "2") (pinfunction "2_2") (pintype "passive"))
      (node (ref "IC53") (pin "6") (pinfunction "AVdd_6") (pintype "passive"))
      (node (ref "IC53") (pin "7") (pinfunction "AVdd_7") (pintype "passive"))
    )
    (net (code "28") (name "Net-(C819-Pad1)") (class "Default")
      (node (ref "C819") (pin "1") (pinfunction "1_1") (pintype "passive"))
      (node (ref "C820") (pin "2") (pinfunction "2_2") (pintype "passive"))
      (node (ref "R393") (pin "2") (pinfunction "2_2") (pintype "passive"))
    )
    (net (code "29") (name "Net-(C820-Pad1)") (class "Default")
      (node (ref "C820") (pin "1") (pinfunction "1_1") (pintype "passive"))
      (node (ref "R389") (pin "2") (pinfunction "2_2") (pintype "passive"))
    )
    (net (code "30") (name "Net-(C822-Pad2)") (class "Default")
      (node (ref "C822") (pin "2") (pinfunction "2_2") (pintype "passive"))
      (node (ref "R390") (pin "1") (pinfunction "1_1") (pintype "passive"))
      (node (ref "R391") (pin "2") (pinfunction "2_2") (pintype "passive"))
    )
    (net (code "31") (name "Net-(C823-Pad1)") (class "Default")
      (node (ref "C823") (pin "1") (pinfunction "1_1") (pintype "passive"))
      (node (ref "R398") (pin "2") (pinfunction "2_2") (pintype "passive"))
    )
    (net (code "32") (name "Net-(C828-Pad2)") (class "Default")
      (node (ref "C828") (pin "2") (pinfunction "2_2") (pintype "passive"))
      (node (ref "R394") (pin "1") (pinfunction "1_1") (pintype "passive"))
      (node (ref "R395") (pin "2") (pinfunction "2_2") (pintype "passive"))
    )
    (net (code "33") (name "Net-(FR98-Pad2)") (class "Default")
      (node (ref "FR98") (pin "2") (pinfunction "2_2") (pintype "passive"))
      (node (ref "R365") (pin "1") (pinfunction "1_1") (pintype "passive"))
      (node (ref "R380") (pin "2") (pinfunction "2_2") (pintype "passive"))
      (node (ref "R382") (pin "1") (pinfunction "1_1") (pintype "passive"))
    )
    (net (code "34") (name "Net-(FR100-Pad1)") (class "Default")
      (node (ref "FR100") (pin "1") (pinfunction "1_1") (pintype "passive"))
      (node (ref "R381") (pin "2") (pinfunction "2_2") (pintype "passive"))
      (node (ref "R383") (pin "1") (pinfunction "1_1") (pintype "passive"))
    )
    (net (code "35") (name "Net-(IC52-CLKin0)") (class "Default")
      (node (ref "C783") (pin "1") (pinfunction "1_1") (pintype "passive"))
      (node (ref "IC52") (pin "13") (pinfunction "CLKin0_13") (pintype "input"))
    )
    (net (code "36") (name "Net-(IC52-CLKin0*)") (class "Default")
      (node (ref "C784") (pin "2") (pinfunction "2_2") (pintype "passive"))
      (node (ref "IC52") (pin "14") (pinfunction "CLKin0*_14") (pintype "input"))
    )
    (net (code "37") (name "Net-(IC52-CLKin1)") (class "Default")
      (node (ref "C786") (pin "1") (pinfunction "1_1") (pintype "passive"))
      (node (ref "IC52") (pin "28") (pinfunction "CLKin1_28") (pintype "input"))
    )
    (net (code "38") (name "Net-(IC52-CLKin1*)") (class "Default")
      (node (ref "C790") (pin "2") (pinfunction "2_2") (pintype "passive"))
      (node (ref "IC52") (pin "27") (pinfunction "CLKin1*_27") (pintype "input"))
    )
    (net (code "39") (name "Net-(IC52-CLKout0)") (class "Default")
      (node (ref "IC52") (pin "1") (pinfunction "CLKout0_1") (pintype "output"))
      (node (ref "R367") (pin "2") (pinfunction "2_2") (pintype "passive"))
    )
    (net (code "40") (name "Net-(IC52-CLKout1)") (class "Default")
      (node (ref "IC52") (pin "3") (pinfunction "CLKout1_3") (pintype "output"))
      (node (ref "R369") (pin "2") (pinfunction "2_2") (pintype "passive"))
    )
    (net (code "41") (name "Net-(IC52-CLKout2)") (class "Default")
      (node (ref "IC52") (pin "5") (pinfunction "CLKout2_5") (pintype "output"))
      (node (ref "R370") (pin "2") (pinfunction "2_2") (pintype "passive"))
    )
    (net (code "42") (name "Net-(IC52-CLKout3)") (class "Default")
      (node (ref "IC52") (pin "7") (pinfunction "CLKout3_7") (pintype "output"))
      (node (ref "R373") (pin "2") (pinfunction "2_2") (pintype "passive"))
    )
    (net (code "43") (name "Net-(IC52-OE)") (class "Default")
      (node (ref "IC52") (pin "31") (pinfunction "OE_31") (pintype "input"))
      (node (ref "R377") (pin "2") (pinfunction "2_2") (pintype "passive"))
    )
    (net (code "44") (name "Net-(IC52-SEL0)") (class "Default")
      (node (ref "IC52") (pin "30") (pinfunction "SEL0_30") (pintype "input"))
      (node (ref "R375") (pin "1") (pinfunction "1_1") (pintype "passive"))
    )
    (net (code "45") (name "Net-(IC53-CE)") (class "Default")
      (node (ref "IC53") (pin "11") (pinfunction "CE_11") (pintype "passive"))
      (node (ref "R388") (pin "1") (pinfunction "1_1") (pintype "passive"))
    )
    (net (code "46") (name "Net-(IC53-CLK)") (class "Default")
      (node (ref "C829") (pin "2") (pinfunction "2_2") (pintype "passive"))
      (node (ref "IC53") (pin "12") (pinfunction "CLK_12") (pintype "passive"))
      (node (ref "R401") (pin "2") (pinfunction "2_2") (pintype "passive"))
    )
    (net (code "47") (name "Net-(IC53-CP)") (class "Default")
      (node (ref "C823") (pin "2") (pinfunction "2_2") (pintype "passive"))
      (node (ref "C824") (pin "2") (pinfunction "2_2") (pintype "passive"))
      (node (ref "IC53") (pin "20") (pinfunction "CP_20") (pintype "passive"))
      (node (ref "R391") (pin "1") (pinfunction "1_1") (pintype "passive"))
    )
    (net (code "48") (name "Net-(IC53-DATA)") (class "Default")
      (node (ref "IC53") (pin "13") (pinfunction "DATA_13") (pintype "passive"))
      (node (ref "R403") (pin "2") (pinfunction "2_2") (pintype "passive"))
    )
    (net (code "49") (name "Net-(IC53-LE)") (class "Default")
      (node (ref "IC53") (pin "14") (pinfunction "LE_14") (pintype "passive"))
      (node (ref "R407") (pin "2") (pinfunction "2_2") (pintype "passive"))
    )
    (net (code "50") (name "Net-(IC53-MUXOUT)") (class "Default")
      (node (ref "IC53") (pin "15") (pinfunction "MUXOUT_15") (pintype "passive"))
      (node (ref "R392") (pin "2") (pinfunction "2_2") (pintype "passive"))
    )
    (net (code "51") (name "Net-(IC53-RFin)") (class "Default")
      (node (ref "C819") (pin "2") (pinfunction "2_2") (pintype "passive"))
      (node (ref "IC53") (pin "8") (pinfunction "RFin_8") (pintype "passive"))
    )
    (net (code "52") (name "Net-(IC53-RFinA)") (class "Default")
      (node (ref "C809") (pin "1") (pinfunction "1_1") (pintype "passive"))
      (node (ref "IC53") (pin "5") (pinfunction "RFinA_5") (pintype "passive"))
    )
    (net (code "53") (name "Net-(IC53-RFinB)") (class "Default")
      (node (ref "C827") (pin "1") (pinfunction "1_1") (pintype "passive"))
      (node (ref "IC53") (pin "4") (pinfunction "RFinB_4") (pintype "passive"))
    )
    (net (code "54") (name "Net-(IC53-Rset)") (class "Default")
      (node (ref "IC53") (pin "19") (pinfunction "Rset_19") (pintype "passive"))
      (node (ref "R397") (pin "1") (pinfunction "1_1") (pintype "passive"))
    )
    (net (code "55") (name "Net-(IC53-Vp)") (class "Default")
      (node (ref "C817") (pin "2") (pinfunction "2_2") (pintype "passive"))
      (node (ref "C818") (pin "1") (pinfunction "1_1") (pintype "passive"))
      (node (ref "IC53") (pin "18") (pinfunction "Vp_18") (pintype "passive"))
      (node (ref "R387") (pin "1") (pinfunction "1_1") (pintype "passive"))
    )
    (net (code "56") (name "Net-(IC54-DIN)") (class "Default")
      (node (ref "IC54") (pin "7") (pinfunction "DIN_7") (pintype "input"))
      (node (ref "R404") (pin "1") (pinfunction "1_1") (pintype "passive"))
    )
    (net (code "57") (name "Net-(IC54-SCLK)") (class "Default")
      (node (ref "IC54") (pin "6") (pinfunction "SCLK_6") (pintype "input"))
      (node (ref "R402") (pin "1") (pinfunction "1_1") (pintype "passive"))
    )
    (net (code "58") (name "Net-(IC54-Vdd)") (class "Default")
      (node (ref "C821") (pin "2") (pinfunction "2_2") (pintype "passive"))
      (node (ref "C825") (pin "1") (pinfunction "1_1") (pintype "passive"))
      (node (ref "C826") (pin "1") (pinfunction "1_1") (pintype "passive"))
      (node (ref "FR102") (pin "1") (pinfunction "1_1") (pintype "passive"))
      (node (ref "IC54") (pin "1") (pinfunction "Vdd_1") (pintype "power_in"))
      (node (ref "R406") (pin "2") (pinfunction "2_2") (pintype "passive"))
    )
    (net (code "59") (name "Net-(IC54-Vfb)") (class "Default")
      (node (ref "C830") (pin "1") (pinfunction "1_1") (pintype "passive"))
      (node (ref "IC54") (pin "3") (pinfunction "Vfb_3") (pintype "input"))
      (node (ref "IC54") (pin "4") (pinfunction "Vout_4") (pintype "output"))
      (node (ref "R394") (pin "2") (pinfunction "2_2") (pintype "passive"))
    )
    (net (code "60") (name "Net-(IC54-~{SYN}C)") (class "Default")
      (node (ref "IC54") (pin "5") (pinfunction "~{SYN}C_5") (pintype "input"))
      (node (ref "R400") (pin "1") (pinfunction "1_1") (pintype "passive"))
    )
    (net (code "61") (name "Net-(J35-X)") (class "Default")
      (node (ref "J35") (pin "1") (pinfunction "X_1") (pintype "passive"))
      (node (ref "R378") (pin "1") (pinfunction "1_1") (pintype "passive"))
    )
    (net (code "62") (name "Net-(R382-Pad2)") (class "Default")
      (node (ref "R382") (pin "2") (pinfunction "2_2") (pintype "passive"))
      (node (ref "R385") (pin "1") (pinfunction "1_1") (pintype "passive"))
    )
    (net (code "63") (name "Net-(XO1-Output)") (class "Default")
      (node (ref "R364") (pin "2") (pinfunction "2_2") (pintype "passive"))
      (node (ref "XO1") (pin "3") (pinfunction "Output_3") (pintype "output"))
    )
    (net (code "64") (name "Net-(XO1-Vcc)") (class "Default")
      (node (ref "C787") (pin "2") (pinfunction "2_2") (pintype "passive"))
      (node (ref "C788") (pin "2") (pinfunction "2_2") (pintype "passive"))
      (node (ref "C789") (pin "1") (pinfunction "1_1") (pintype "passive"))
      (node (ref "R365") (pin "2") (pinfunction "2_2") (pintype "passive"))
      (node (ref "XO1") (pin "4") (pinfunction "Vcc_4") (pintype "power_in"))
    )
    (net (code "65") (name "Net-(XO2-OUT)") (class "Default")
      (node (ref "R379") (pin "2") (pinfunction "2_2") (pintype "passive"))
      (node (ref "XO2") (pin "4") (pinfunction "OUT_4") (pintype "passive"))
      (node (ref "XO3") (pin "3") (pinfunction "OUT_3") (pintype "passive"))
    )
    (net (code "66") (name "Net-(XO2-TRI-ST.)") (class "Default")
      (node (ref "R376") (pin "1") (pinfunction "1_1") (pintype "passive"))
      (node (ref "XO2") (pin "6") (pinfunction "TRI-ST._6") (pintype "passive"))
    )
    (net (code "67") (name "Net-(XO2-VDD)") (class "Default")
      (node (ref "C795") (pin "2") (pinfunction "2_2") (pintype "passive"))
      (node (ref "C796") (pin "2") (pinfunction "2_2") (pintype "passive"))
      (node (ref "R376") (pin "2") (pinfunction "2_2") (pintype "passive"))
      (node (ref "R380") (pin "1") (pinfunction "1_1") (pintype "passive"))
      (node (ref "XO2") (pin "5") (pinfunction "VDD_5") (pintype "passive"))
      (node (ref "XO3") (pin "4") (pinfunction "VDD_4") (pintype "passive"))
    )
    (net (code "68") (name "Net-(XO4-RF_OUT)") (class "Default")
      (node (ref "R384") (pin "1") (pinfunction "1_1") (pintype "passive"))
      (node (ref "XO4") (pin "6") (pinfunction "RF_OUT_6") (pintype "output"))
    )
    (net (code "69") (name "Net-(XO4-VCC)") (class "Default")
      (node (ref "C806") (pin "2") (pinfunction "2_2") (pintype "passive"))
      (node (ref "C807") (pin "2") (pinfunction "2_2") (pintype "passive"))
      (node (ref "R385") (pin "2") (pinfunction "2_2") (pintype "passive"))
      (node (ref "XO4") (pin "9") (pinfunction "VCC_9") (pintype "power_in"))
    )
    (net (code "70") (name "Net-(XO4-VC_FILTER)") (class "Default")
      (node (ref "C808") (pin "2") (pinfunction "2_2") (pintype "passive"))
      (node (ref "XO4") (pin "7") (pinfunction "VC_FILTER_7") (pintype "input"))
    )
    (net (code "71") (name "VCC1P8") (class "Default")
      (node (ref "R405") (pin "2") (pinfunction "2_2") (pintype "passive"))
    )
    (net (code "72") (name "VCC1P8_LMS1_B") (class "Default")
      (node (ref "R381") (pin "1") (pinfunction "1_1") (pintype "passive"))
    )
    (net (code "73") (name "VCC1P8_LMS2_B") (class "Default")
      (node (ref "R383") (pin "2") (pinfunction "2_2") (pintype "passive"))
    )
    (net (code "74") (name "VCC2P5") (class "Default")
      (node (ref "R399") (pin "2") (pinfunction "2_2") (pintype "passive"))
      (node (ref "R408") (pin "2") (pinfunction "2_2") (pintype "passive"))
    )
    (net (code "75") (name "VCC3P3_CLK") (class "Default")
      (node (ref "C811") (pin "2") (pinfunction "2_2") (pintype "passive"))
      (node (ref "C815") (pin "1") (pinfunction "1_1") (pintype "passive"))
      (node (ref "C816") (pin "1") (pinfunction "1_1") (pintype "passive"))
      (node (ref "FR101") (pin "1") (pinfunction "1_1") (pintype "passive"))
      (node (ref "FR99") (pin "1") (pinfunction "1_1") (pintype "passive"))
      (node (ref "IC53") (pin "16") (pinfunction "DVdd_16") (pintype "passive"))
      (node (ref "IC53") (pin "17") (pinfunction "DVdd_17") (pintype "passive"))
      (node (ref "R387") (pin "2") (pinfunction "2_2") (pintype "passive"))
      (node (ref "R388") (pin "2") (pinfunction "2_2") (pintype "passive"))
    )
    (net (code "76") (name "VCC3P3_XO") (class "Default")
      (node (ref "FR102") (pin "2") (pinfunction "2_2") (pintype "passive"))
      (node (ref "FR98") (pin "1") (pinfunction "1_1") (pintype "passive"))
    )
    (net (code "77") (name "unconnected-(IC52-CLKout7-Pad20)") (class "Default")
      (node (ref "IC52") (pin "20") (pinfunction "CLKout7_20") (pintype "output+no_connect"))
    )
    (net (code "78") (name "unconnected-(IC52-CLKout8-Pad22)") (class "Default")
      (node (ref "IC52") (pin "22") (pinfunction "CLKout8_22") (pintype "output+no_connect"))
    )
    (net (code "79") (name "unconnected-(IC52-OSCin-Pad11)") (class "Default")
      (node (ref "IC52") (pin "11") (pinfunction "OSCin_11") (pintype "input+no_connect"))
    )
    (net (code "80") (name "unconnected-(IC52-OSCout-Pad12)") (class "Default")
      (node (ref "IC52") (pin "12") (pinfunction "OSCout_12") (pintype "output+no_connect"))
    )
    (net (code "81") (name "unconnected-(XO2-T.S.-Pad3)") (class "Default")
      (node (ref "XO2") (pin "3") (pinfunction "T.S._3") (pintype "passive+no_connect"))
    )
    (net (code "82") (name "unconnected-(XO4-NC-Pad2)") (class "Default")
      (node (ref "XO4") (pin "2") (pinfunction "NC_2") (pintype "passive+no_connect"))
    )
    (net (code "83") (name "unconnected-(XO4-NC-Pad3)") (class "Default")
      (node (ref "XO4") (pin "3") (pinfunction "NC_3") (pintype "passive+no_connect"))
    )
    (net (code "84") (name "unconnected-(XO4-NC-Pad5)") (class "Default")
      (node (ref "XO4") (pin "5") (pinfunction "NC_5") (pintype "passive+no_connect"))
    )
    (net (code "85") (name "unconnected-(XO4-NC-Pad8)") (class "Default")
      (node (ref "XO4") (pin "8") (pinfunction "NC_8") (pintype "passive+no_connect"))
    )
    (net (code "86") (name "unconnected-(XO4-NC-Pad10)") (class "Default")
      (node (ref "XO4") (pin "10") (pinfunction "NC_10") (pintype "passive+no_connect"))
    )
  )
)
